# SENSOR_SCH.net
KiCad netlist of a schematic drawn in EasyEDA
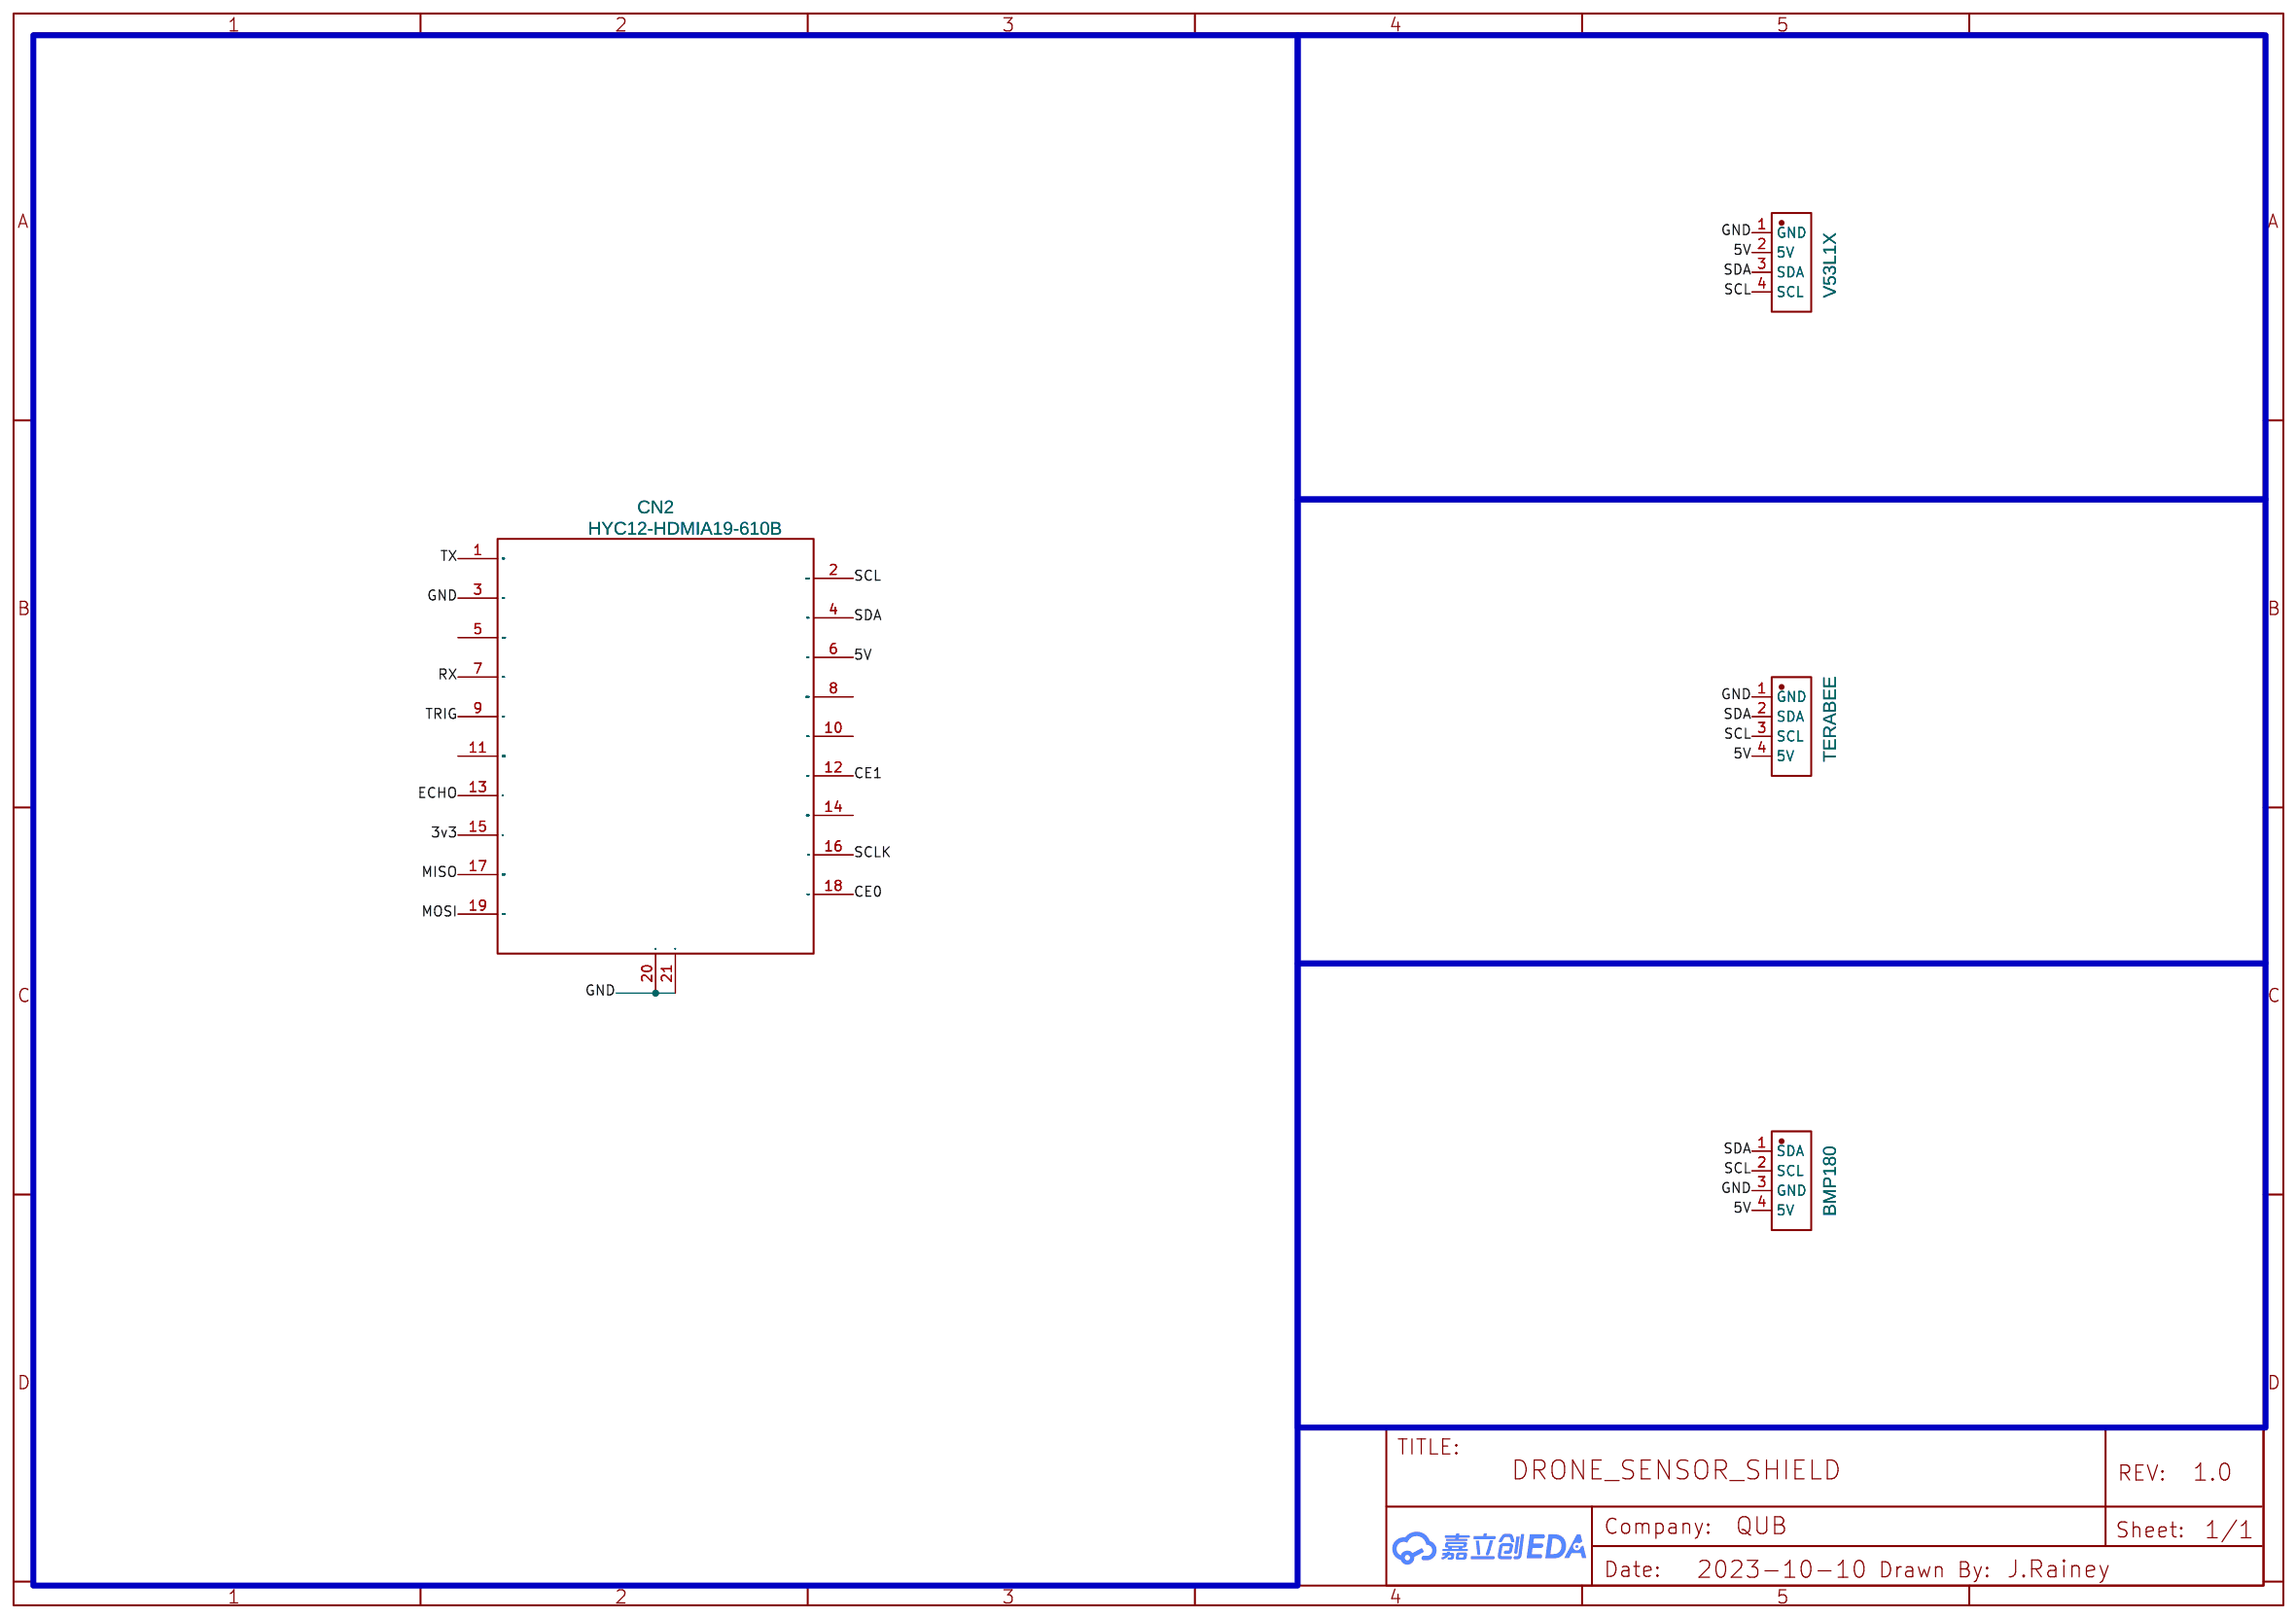
[diagram p0: schematic sheet]

(export (version "E")
  (design (tool "Eeschema 10.0.6"))
  (components
    (comp (ref "BMP180")
      (value "PZ254V-11-04P")
      (fields (field (name "BOM_Supplier Part") "C492403"))
      (libsource (lib "") (part "PZ254V-11-04P_2"))
    )
    (comp (ref "CN2")
      (value "HYC12-HDMIA19-610B")
      (fields (field (name "BOM_Supplier Part") "C711354"))
      (libsource (lib "") (part "HYC12-HDMIA19-610B"))
    )
    (comp (ref "TERABEE")
      (value "PZ254V-11-04P")
      (fields (field (name "BOM_Supplier Part") "C492403"))
      (libsource (lib "") (part "PZ254V-11-04P_1"))
    )
    (comp (ref "V53L1X")
      (value "PZ254V-11-04P")
      (fields (field (name "BOM_Supplier Part") "C492403"))
      (libsource (lib "") (part "PZ254V-11-04P"))
    )
  )
  (nets
    (net (code "1") (name "/3v3") (class "Default")
      (node (ref "CN2") (pin "15") (pinfunction "SCL_15") (pintype "unspecified"))
    )
    (net (code "2") (name "/5V") (class "Default")
      (node (ref "BMP180") (pin "4") (pinfunction "5V_4") (pintype "unspecified"))
      (node (ref "CN2") (pin "6") (pinfunction "TMDS_Data_1-_6") (pintype "unspecified"))
      (node (ref "TERABEE") (pin "4") (pinfunction "5V_4") (pintype "unspecified"))
      (node (ref "V53L1X") (pin "2") (pinfunction "5V_2") (pintype "unspecified"))
    )
    (net (code "3") (name "/CE0") (class "Default")
      (node (ref "CN2") (pin "18") (pinfunction "+5V_Power_18") (pintype "unspecified"))
    )
    (net (code "4") (name "/CE1") (class "Default")
      (node (ref "CN2") (pin "12") (pinfunction "TMDS_Clock-_12") (pintype "unspecified"))
    )
    (net (code "5") (name "/ECHO") (class "Default")
      (node (ref "CN2") (pin "13") (pinfunction "CEC_13") (pintype "unspecified"))
    )
    (net (code "6") (name "/GND") (class "Default")
      (node (ref "BMP180") (pin "3") (pinfunction "GND_3") (pintype "unspecified"))
      (node (ref "CN2") (pin "20") (pinfunction "EH_20") (pintype "unspecified"))
      (node (ref "CN2") (pin "21") (pinfunction "EH_21") (pintype "unspecified"))
      (node (ref "CN2") (pin "3") (pinfunction "TMDS_Data_2-_3") (pintype "unspecified"))
      (node (ref "TERABEE") (pin "1") (pinfunction "GND_1") (pintype "unspecified"))
      (node (ref "V53L1X") (pin "1") (pinfunction "GND_1") (pintype "unspecified"))
    )
    (net (code "7") (name "/MISO") (class "Default")
      (node (ref "CN2") (pin "17") (pinfunction "DDC/CEC_Ground_17") (pintype "unspecified"))
    )
    (net (code "8") (name "/MOSI") (class "Default")
      (node (ref "CN2") (pin "19") (pinfunction "Hot_Plug_Detect_19") (pintype "unspecified"))
    )
    (net (code "9") (name "/RX") (class "Default")
      (node (ref "CN2") (pin "7") (pinfunction "TMDS_Data_0+_7") (pintype "unspecified"))
    )
    (net (code "10") (name "/SCL") (class "Default")
      (node (ref "BMP180") (pin "2") (pinfunction "SCL_2") (pintype "unspecified"))
      (node (ref "CN2") (pin "2") (pinfunction "TMDS_Data_2_Shield_2") (pintype "unspecified"))
      (node (ref "TERABEE") (pin "3") (pinfunction "SCL_3") (pintype "unspecified"))
      (node (ref "V53L1X") (pin "4") (pinfunction "SCL_4") (pintype "unspecified"))
    )
    (net (code "11") (name "/SCLK") (class "Default")
      (node (ref "CN2") (pin "16") (pinfunction "SDA_16") (pintype "unspecified"))
    )
    (net (code "12") (name "/SDA") (class "Default")
      (node (ref "BMP180") (pin "1") (pinfunction "SDA_1") (pintype "unspecified"))
      (node (ref "CN2") (pin "4") (pinfunction "TMDS_Data_1+_4") (pintype "unspecified"))
      (node (ref "TERABEE") (pin "2") (pinfunction "SDA_2") (pintype "unspecified"))
      (node (ref "V53L1X") (pin "3") (pinfunction "SDA_3") (pintype "unspecified"))
    )
    (net (code "13") (name "/TRIG") (class "Default")
      (node (ref "CN2") (pin "9") (pinfunction "TMDS_Data_0-_9") (pintype "unspecified"))
    )
    (net (code "14") (name "/TX") (class "Default")
      (node (ref "CN2") (pin "1") (pinfunction "TMDS_Data_2+_1") (pintype "unspecified"))
    )
    (net (code "15") (name "unconnected-(CN2-Reserved_(N.C.)-Pad14)") (class "Default")
      (node (ref "CN2") (pin "14") (pinfunction "Reserved_(N.C.)_14") (pintype "unspecified"))
    )
    (net (code "16") (name "unconnected-(CN2-TMDS_Clock+-Pad10)") (class "Default")
      (node (ref "CN2") (pin "10") (pinfunction "TMDS_Clock+_10") (pintype "unspecified"))
    )
    (net (code "17") (name "unconnected-(CN2-TMDS_Clock_Shield-Pad11)") (class "Default")
      (node (ref "CN2") (pin "11") (pinfunction "TMDS_Clock_Shield_11") (pintype "unspecified"))
    )
    (net (code "18") (name "unconnected-(CN2-TMDS_Data_0_Shield-Pad8)") (class "Default")
      (node (ref "CN2") (pin "8") (pinfunction "TMDS_Data_0_Shield_8") (pintype "unspecified"))
    )
    (net (code "19") (name "unconnected-(CN2-TMDS_Data_1_Shield-Pad5)") (class "Default")
      (node (ref "CN2") (pin "5") (pinfunction "TMDS_Data_1_Shield_5") (pintype "unspecified"))
    )
  )
)
